# bmsMaster_led.net
KiCad netlist of a schematic drawn in Altium Designer
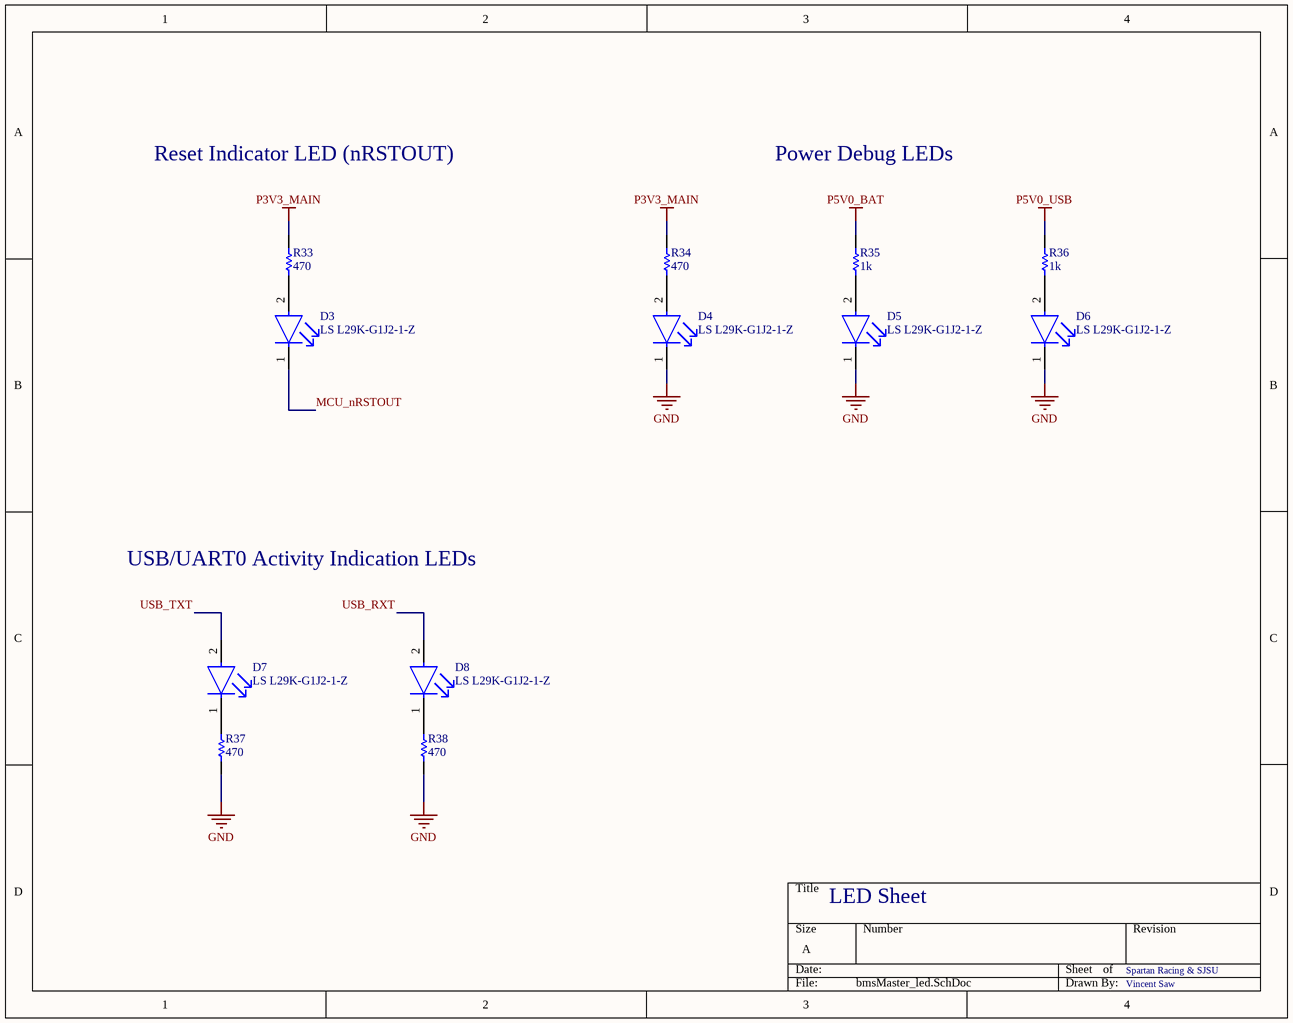
[diagram p0: bmsMaster_led.SchDoc]

(export (version "E")
  (design (tool "Eeschema 10.0.6"))
  (components
    (comp (ref "D3")
      (value "LS L29K-G1J2-1-Z")
      (footprint "FP-LS_L29K-MFG")
      (description "LED RED DIFFUSED 0603 SMD")
      (fields
        (field (name "MANUFACTURER") "Osram Opto")
        (field (name "OCTOPART") "https://octopart.com/ls+l29k-g1j2-1-z-osram+opto-31093939")
      )
      (libsource (lib "Altium Content Vault") (part "8706943c75ba83719d021d2fdc84c58"))
    )
    (comp (ref "D4")
      (value "LS L29K-G1J2-1-Z")
      (footprint "FP-LS_L29K-MFG")
      (description "LED RED DIFFUSED 0603 SMD")
      (fields
        (field (name "MANUFACTURER") "Osram Opto")
        (field (name "OCTOPART") "https://octopart.com/ls+l29k-g1j2-1-z-osram+opto-31093939")
      )
      (libsource (lib "Altium Content Vault") (part "8706943c75ba83719d021d2fdc84c58"))
    )
    (comp (ref "D5")
      (value "LS L29K-G1J2-1-Z")
      (footprint "FP-LS_L29K-MFG")
      (description "LED RED DIFFUSED 0603 SMD")
      (fields
        (field (name "MANUFACTURER") "Osram Opto")
        (field (name "OCTOPART") "https://octopart.com/ls+l29k-g1j2-1-z-osram+opto-31093939")
      )
      (libsource (lib "Altium Content Vault") (part "8706943c75ba83719d021d2fdc84c58"))
    )
    (comp (ref "D6")
      (value "LS L29K-G1J2-1-Z")
      (footprint "FP-LS_L29K-MFG")
      (description "LED RED DIFFUSED 0603 SMD")
      (fields
        (field (name "MANUFACTURER") "Osram Opto")
        (field (name "OCTOPART") "https://octopart.com/ls+l29k-g1j2-1-z-osram+opto-31093939")
      )
      (libsource (lib "Altium Content Vault") (part "8706943c75ba83719d021d2fdc84c58"))
    )
    (comp (ref "D7")
      (value "LS L29K-G1J2-1-Z")
      (footprint "FP-LS_L29K-MFG")
      (description "LED RED DIFFUSED 0603 SMD")
      (fields
        (field (name "MANUFACTURER") "Osram Opto")
        (field (name "OCTOPART") "https://octopart.com/ls+l29k-g1j2-1-z-osram+opto-31093939")
      )
      (libsource (lib "Altium Content Vault") (part "8706943c75ba83719d021d2fdc84c58"))
    )
    (comp (ref "D8")
      (value "LS L29K-G1J2-1-Z")
      (footprint "FP-LS_L29K-MFG")
      (description "LED RED DIFFUSED 0603 SMD")
      (fields
        (field (name "MANUFACTURER") "Osram Opto")
        (field (name "OCTOPART") "https://octopart.com/ls+l29k-g1j2-1-z-osram+opto-31093939")
      )
      (libsource (lib "Altium Content Vault") (part "8706943c75ba83719d021d2fdc84c58"))
    )
    (comp (ref "R33")
      (value "470")
      (footprint "RESC1608X50N")
      (description "Resistor")
      (libsource (lib "Simulation Generic Components") (part "Resistor"))
    )
    (comp (ref "R34")
      (value "470")
      (footprint "RESC1608X50N")
      (description "Resistor")
      (libsource (lib "Simulation Generic Components") (part "Resistor"))
    )
    (comp (ref "R35")
      (value "1k")
      (footprint "RESC1608X50N")
      (description "Resistor")
      (libsource (lib "Simulation Generic Components") (part "Resistor"))
    )
    (comp (ref "R36")
      (value "1k")
      (footprint "RESC1608X50N")
      (description "Resistor")
      (libsource (lib "Simulation Generic Components") (part "Resistor"))
    )
    (comp (ref "R37")
      (value "470")
      (footprint "RESC1608X50N")
      (description "Resistor")
      (libsource (lib "Simulation Generic Components") (part "Resistor"))
    )
    (comp (ref "R38")
      (value "470")
      (footprint "RESC1608X50N")
      (description "Resistor")
      (libsource (lib "Simulation Generic Components") (part "Resistor"))
    )
  )
  (nets
    (net (code "1") (name "/MCU_nRSTOUT") (class "Default")
      (node (ref "D3") (pin "1") (pinfunction "C_1") (pintype "passive"))
    )
    (net (code "2") (name "/USB_RXT") (class "Default")
      (node (ref "D8") (pin "2") (pinfunction "A_2") (pintype "passive"))
    )
    (net (code "3") (name "/USB_TXT") (class "Default")
      (node (ref "D7") (pin "2") (pinfunction "A_2") (pintype "passive"))
    )
    (net (code "4") (name "GND") (class "Default")
      (node (ref "D4") (pin "1") (pinfunction "C_1") (pintype "passive"))
      (node (ref "D5") (pin "1") (pinfunction "C_1") (pintype "passive"))
      (node (ref "D6") (pin "1") (pinfunction "C_1") (pintype "passive"))
      (node (ref "R37") (pin "1") (pinfunction "1_1") (pintype "passive"))
      (node (ref "R38") (pin "1") (pinfunction "1_1") (pintype "passive"))
    )
    (net (code "5") (name "Net-(D3-A)") (class "Default")
      (node (ref "D3") (pin "2") (pinfunction "A_2") (pintype "passive"))
      (node (ref "R33") (pin "1") (pinfunction "1_1") (pintype "passive"))
    )
    (net (code "6") (name "Net-(D4-A)") (class "Default")
      (node (ref "D4") (pin "2") (pinfunction "A_2") (pintype "passive"))
      (node (ref "R34") (pin "1") (pinfunction "1_1") (pintype "passive"))
    )
    (net (code "7") (name "Net-(D5-A)") (class "Default")
      (node (ref "D5") (pin "2") (pinfunction "A_2") (pintype "passive"))
      (node (ref "R35") (pin "1") (pinfunction "1_1") (pintype "passive"))
    )
    (net (code "8") (name "Net-(D6-A)") (class "Default")
      (node (ref "D6") (pin "2") (pinfunction "A_2") (pintype "passive"))
      (node (ref "R36") (pin "1") (pinfunction "1_1") (pintype "passive"))
    )
    (net (code "9") (name "Net-(D7-C)") (class "Default")
      (node (ref "D7") (pin "1") (pinfunction "C_1") (pintype "passive"))
      (node (ref "R37") (pin "2") (pinfunction "2_2") (pintype "passive"))
    )
    (net (code "10") (name "Net-(D8-C)") (class "Default")
      (node (ref "D8") (pin "1") (pinfunction "C_1") (pintype "passive"))
      (node (ref "R38") (pin "2") (pinfunction "2_2") (pintype "passive"))
    )
    (net (code "11") (name "P3V3_MAIN") (class "Default")
      (node (ref "R33") (pin "2") (pinfunction "2_2") (pintype "passive"))
      (node (ref "R34") (pin "2") (pinfunction "2_2") (pintype "passive"))
    )
    (net (code "12") (name "P5V0_BAT") (class "Default")
      (node (ref "R35") (pin "2") (pinfunction "2_2") (pintype "passive"))
    )
    (net (code "13") (name "P5V0_USB") (class "Default")
      (node (ref "R36") (pin "2") (pinfunction "2_2") (pintype "passive"))
    )
  )
)
